# ESP32_breakout_v2_1.net
KiCad netlist of a schematic drawn in EAGLE
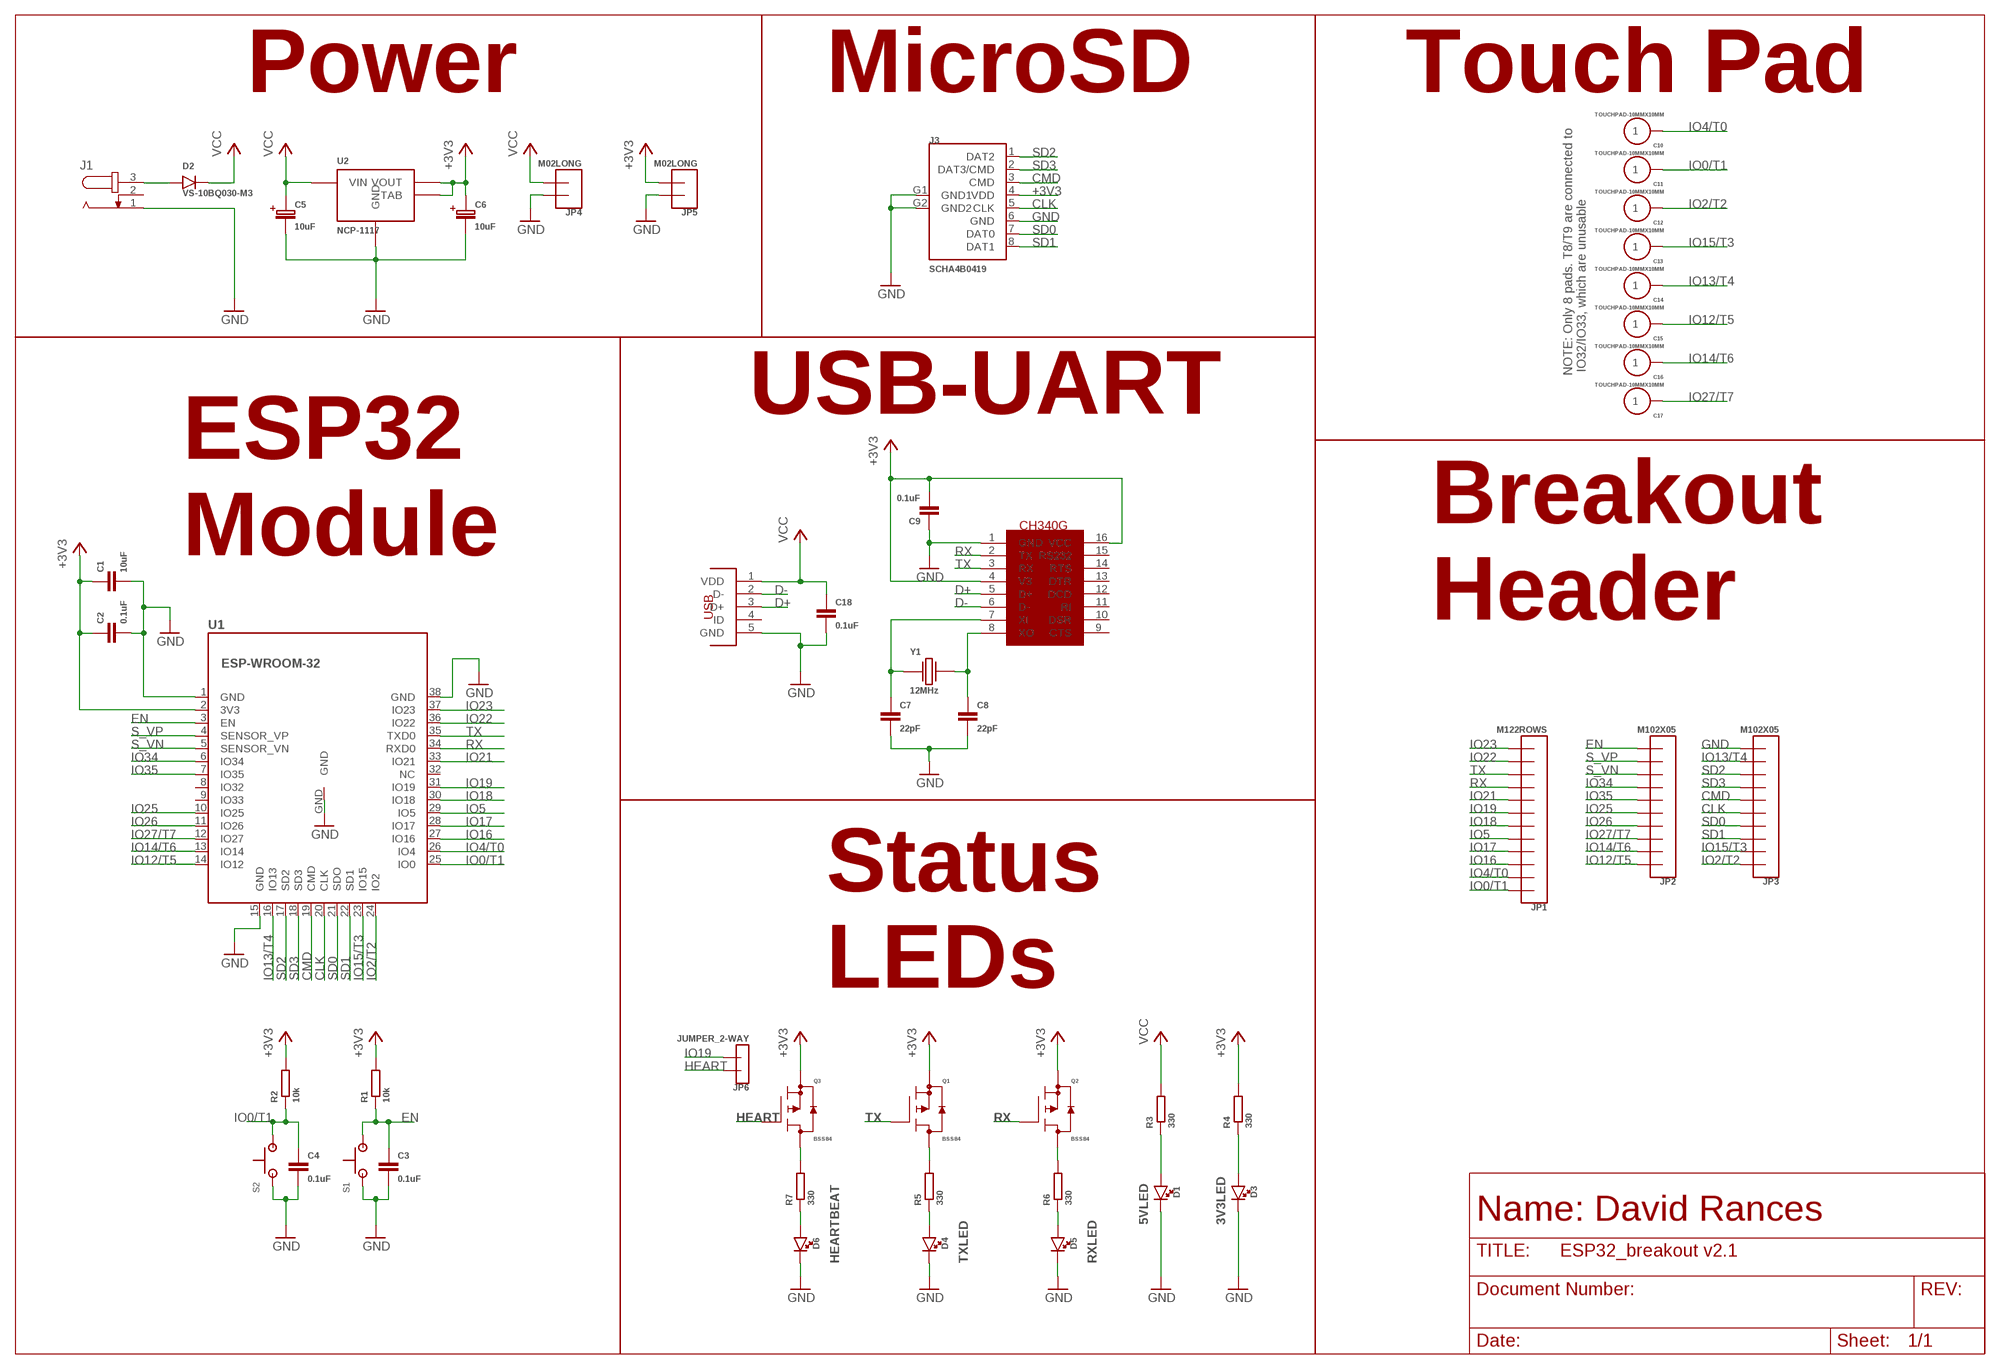
[diagram p0: schematic, sheet 1]

(export (version "E")
  (design (tool "Eeschema 10.0.6"))
  (components
    (comp (ref "C1")
      (value "10uF")
      (footprint "eagle-import:CAP-0603")
      (libsource (lib "eagle-import") (part "CAP0603"))
    )
    (comp (ref "C2")
      (value "0.1uF")
      (footprint "eagle-import:CAP-0603")
      (libsource (lib "eagle-import") (part "CAP0603"))
    )
    (comp (ref "C3")
      (value "0.1uF")
      (footprint "eagle-import:CAP-0603")
      (libsource (lib "eagle-import") (part "CAP0603"))
    )
    (comp (ref "C4")
      (value "0.1uF")
      (footprint "eagle-import:CAP-0603")
      (libsource (lib "eagle-import") (part "CAP0603"))
    )
    (comp (ref "C5")
      (value "10uF")
      (footprint "eagle-import:B-3528")
      (libsource (lib "eagle-import") (part "CAP-POLARCASEB-3528"))
    )
    (comp (ref "C6")
      (value "10uF")
      (footprint "eagle-import:B-3528")
      (libsource (lib "eagle-import") (part "CAP-POLARCASEB-3528"))
    )
    (comp (ref "C7")
      (value "22pF")
      (footprint "eagle-import:CAP-0603")
      (libsource (lib "eagle-import") (part "CAP0603"))
    )
    (comp (ref "C8")
      (value "22pF")
      (footprint "eagle-import:CAP-0603")
      (libsource (lib "eagle-import") (part "CAP0603"))
    )
    (comp (ref "C9")
      (value "0.1uF")
      (footprint "eagle-import:CAP-0603")
      (libsource (lib "eagle-import") (part "CAP0603"))
    )
    (comp (ref "C10")
      (value "TOUCHPAD-10MMX10MM")
      (footprint "eagle-import:TOUCH-10MMX10MM")
      (libsource (lib "eagle-import") (part "TOUCHPAD-10MMX10MM"))
    )
    (comp (ref "C11")
      (value "TOUCHPAD-10MMX10MM")
      (footprint "eagle-import:TOUCH-10MMX10MM")
      (libsource (lib "eagle-import") (part "TOUCHPAD-10MMX10MM"))
    )
    (comp (ref "C12")
      (value "TOUCHPAD-10MMX10MM")
      (footprint "eagle-import:TOUCH-10MMX10MM")
      (libsource (lib "eagle-import") (part "TOUCHPAD-10MMX10MM"))
    )
    (comp (ref "C13")
      (value "TOUCHPAD-10MMX10MM")
      (footprint "eagle-import:TOUCH-10MMX10MM")
      (libsource (lib "eagle-import") (part "TOUCHPAD-10MMX10MM"))
    )
    (comp (ref "C14")
      (value "TOUCHPAD-10MMX10MM")
      (footprint "eagle-import:TOUCH-10MMX10MM")
      (libsource (lib "eagle-import") (part "TOUCHPAD-10MMX10MM"))
    )
    (comp (ref "C15")
      (value "TOUCHPAD-10MMX10MM")
      (footprint "eagle-import:TOUCH-10MMX10MM")
      (libsource (lib "eagle-import") (part "TOUCHPAD-10MMX10MM"))
    )
    (comp (ref "C16")
      (value "TOUCHPAD-10MMX10MM")
      (footprint "eagle-import:TOUCH-10MMX10MM")
      (libsource (lib "eagle-import") (part "TOUCHPAD-10MMX10MM"))
    )
    (comp (ref "C17")
      (value "TOUCHPAD-10MMX10MM")
      (footprint "eagle-import:TOUCH-10MMX10MM")
      (libsource (lib "eagle-import") (part "TOUCHPAD-10MMX10MM"))
    )
    (comp (ref "C18")
      (value "0.1uF")
      (footprint "eagle-import:CAP-0603")
      (libsource (lib "eagle-import") (part "CAP0603"))
    )
    (comp (ref "D1")
      (value "LED1206")
      (footprint "eagle-import:LED-1206")
      (libsource (lib "eagle-import") (part "LED1206"))
    )
    (comp (ref "D2")
      (value "VS-10BQ030-M3")
      (footprint "eagle-import:DO-214AA")
      (libsource (lib "eagle-import") (part "VS-10BQ030-M3"))
    )
    (comp (ref "D3")
      (value "LED1206")
      (footprint "eagle-import:LED-1206")
      (libsource (lib "eagle-import") (part "LED1206"))
    )
    (comp (ref "D4")
      (value "LED1206")
      (footprint "eagle-import:LED-1206")
      (libsource (lib "eagle-import") (part "LED1206"))
    )
    (comp (ref "D5")
      (value "LED1206")
      (footprint "eagle-import:LED-1206")
      (libsource (lib "eagle-import") (part "LED1206"))
    )
    (comp (ref "D6")
      (value "LED1206")
      (footprint "eagle-import:LED-1206")
      (libsource (lib "eagle-import") (part "LED1206"))
    )
    (comp (ref "J1")
      (value "JACK-PLUG0")
      (footprint "eagle-import:SPC4077")
      (libsource (lib "eagle-import") (part "JACK-PLUG0"))
    )
    (comp (ref "J3")
      (value "SCHA4B0419")
      (footprint "eagle-import:MICROSD_SCHA4B0419")
      (libsource (lib "eagle-import") (part "SCHA4B0419"))
    )
    (comp (ref "JP1")
      (value "M122ROWS")
      (footprint "eagle-import:2X06")
      (libsource (lib "eagle-import") (part "M122ROWS"))
    )
    (comp (ref "JP2")
      (value "M102X05")
      (footprint "eagle-import:2X05")
      (libsource (lib "eagle-import") (part "M102X05"))
    )
    (comp (ref "JP3")
      (value "M102X05")
      (footprint "eagle-import:2X05")
      (libsource (lib "eagle-import") (part "M102X05"))
    )
    (comp (ref "JP4")
      (value "M02LONG")
      (footprint "eagle-import:1X02-LONG")
      (libsource (lib "eagle-import") (part "M02LONG"))
    )
    (comp (ref "JP5")
      (value "M02LONG")
      (footprint "eagle-import:1X02-LONG")
      (libsource (lib "eagle-import") (part "M02LONG"))
    )
    (comp (ref "JP6")
      (value "JUMPER_2-WAY")
      (footprint "eagle-import:1X02")
      (libsource (lib "eagle-import") (part "JUMPER_2-WAY"))
    )
    (comp (ref "Q1")
      (value "BSS84")
      (footprint "eagle-import:SOT-23-3")
      (libsource (lib "eagle-import") (part "BSS84"))
    )
    (comp (ref "Q2")
      (value "BSS84")
      (footprint "eagle-import:SOT-23-3")
      (libsource (lib "eagle-import") (part "BSS84"))
    )
    (comp (ref "Q3")
      (value "BSS84")
      (footprint "eagle-import:SOT-23-3")
      (libsource (lib "eagle-import") (part "BSS84"))
    )
    (comp (ref "R1")
      (value "10k")
      (footprint "eagle-import:RES-0603")
      (libsource (lib "eagle-import") (part "RESISTOR0603"))
    )
    (comp (ref "R2")
      (value "10k")
      (footprint "eagle-import:RES-0603")
      (libsource (lib "eagle-import") (part "RESISTOR0603"))
    )
    (comp (ref "R3")
      (value "330")
      (footprint "eagle-import:RES-0805")
      (libsource (lib "eagle-import") (part "RESISTOR0805"))
    )
    (comp (ref "R4")
      (value "330")
      (footprint "eagle-import:RES-0805")
      (libsource (lib "eagle-import") (part "RESISTOR0805"))
    )
    (comp (ref "R5")
      (value "330")
      (footprint "eagle-import:RES-0805")
      (libsource (lib "eagle-import") (part "RESISTOR0805"))
    )
    (comp (ref "R6")
      (value "330")
      (footprint "eagle-import:RES-0805")
      (libsource (lib "eagle-import") (part "RESISTOR0805"))
    )
    (comp (ref "R7")
      (value "330")
      (footprint "eagle-import:RES-0805")
      (libsource (lib "eagle-import") (part "RESISTOR0805"))
    )
    (comp (ref "S1")
      (value "PUSHBUTTONSKHMQME010")
      (footprint "eagle-import:SKHMQME010")
      (libsource (lib "eagle-import") (part "PUSHBUTTONSKHMQME010"))
    )
    (comp (ref "S2")
      (value "PUSHBUTTONSKHMQME010")
      (footprint "eagle-import:SKHMQME010")
      (libsource (lib "eagle-import") (part "PUSHBUTTONSKHMQME010"))
    )
    (comp (ref "U$4")
      (value "MOLEX_USBMICRO")
      (footprint "eagle-import:MOLEX_47346-001")
      (libsource (lib "eagle-import") (part "MOLEX_USBMICRO"))
    )
    (comp (ref "U$7")
      (value "CH340G")
      (footprint "eagle-import:SOIC16")
      (libsource (lib "eagle-import") (part "CH340G"))
    )
    (comp (ref "U1")
      (value "ESP-WROOM-32")
      (footprint "eagle-import:ESP-WROOM-32")
      (libsource (lib "eagle-import") (part "ESP-WROOM-32"))
    )
    (comp (ref "U2")
      (value "NCP-1117")
      (footprint "eagle-import:SOT-223-4")
      (libsource (lib "eagle-import") (part "NCP-1117"))
    )
    (comp (ref "Y1")
      (value "12MHz")
      (footprint "eagle-import:HC-49_US")
      (libsource (lib "eagle-import") (part "ABLS-12MHZ-B2-T"))
    )
  )
  (nets
    (net (code "1") (name "+3V3") (class "Default")
      (node (ref "C1") (pin "1") (pinfunction "1_1") (pintype "passive"))
      (node (ref "C2") (pin "1") (pinfunction "1_1") (pintype "passive"))
      (node (ref "C6") (pin "P") (pinfunction "P_P") (pintype "passive"))
      (node (ref "C9") (pin "2") (pinfunction "2_2") (pintype "passive"))
      (node (ref "J3") (pin "4") (pinfunction "VDD_4") (pintype "bidirectional"))
      (node (ref "JP5") (pin "2") (pinfunction "2_2") (pintype "bidirectional"))
      (node (ref "Q1") (pin "S") (pinfunction "S_S") (pintype "bidirectional"))
      (node (ref "Q2") (pin "S") (pinfunction "S_S") (pintype "bidirectional"))
      (node (ref "Q3") (pin "S") (pinfunction "S_S") (pintype "bidirectional"))
      (node (ref "R1") (pin "2") (pinfunction "2_2") (pintype "passive"))
      (node (ref "R2") (pin "2") (pinfunction "2_2") (pintype "passive"))
      (node (ref "R4") (pin "2") (pinfunction "2_2") (pintype "passive"))
      (node (ref "U$7") (pin "16") (pinfunction "VCC_16") (pintype "bidirectional"))
      (node (ref "U$7") (pin "4") (pinfunction "V3_4") (pintype "bidirectional"))
      (node (ref "U1") (pin "2") (pinfunction "3V3_2") (pintype "bidirectional"))
      (node (ref "U2") (pin "2") (pinfunction "VOUT_2") (pintype "power_in"))
      (node (ref "U2") (pin "PAD") (pinfunction "TAB_PAD") (pintype "power_in"))
    )
    (net (code "2") (name "/CLK") (class "Default")
      (node (ref "J3") (pin "5") (pinfunction "CLK_5") (pintype "bidirectional"))
      (node (ref "JP3") (pin "5") (pinfunction "5_5") (pintype "bidirectional"))
      (node (ref "U1") (pin "20") (pinfunction "CLK_20") (pintype "bidirectional"))
    )
    (net (code "3") (name "/CMD") (class "Default")
      (node (ref "J3") (pin "3") (pinfunction "CMD_3") (pintype "bidirectional"))
      (node (ref "JP3") (pin "6") (pinfunction "6_6") (pintype "bidirectional"))
      (node (ref "U1") (pin "19") (pinfunction "CMD_19") (pintype "bidirectional"))
    )
    (net (code "4") (name "/D+") (class "Default")
      (node (ref "U$4") (pin "3") (pinfunction "D+_3") (pintype "bidirectional"))
      (node (ref "U$7") (pin "5") (pinfunction "D+_5") (pintype "bidirectional"))
    )
    (net (code "5") (name "/D-") (class "Default")
      (node (ref "U$4") (pin "2") (pinfunction "D-_2") (pintype "bidirectional"))
      (node (ref "U$7") (pin "6") (pinfunction "D-_6") (pintype "bidirectional"))
    )
    (net (code "6") (name "/EN") (class "Default")
      (node (ref "C3") (pin "1") (pinfunction "1_1") (pintype "passive"))
      (node (ref "JP2") (pin "10") (pinfunction "10_10") (pintype "bidirectional"))
      (node (ref "R1") (pin "1") (pinfunction "1_1") (pintype "passive"))
      (node (ref "S1") (pin "3") (pinfunction "2_3") (pintype "bidirectional"))
      (node (ref "S1") (pin "4") (pinfunction "2_4") (pintype "bidirectional"))
      (node (ref "U1") (pin "3") (pinfunction "EN_3") (pintype "bidirectional"))
    )
    (net (code "7") (name "/HEART") (class "Default")
      (node (ref "JP6") (pin "1") (pinfunction "1_1") (pintype "bidirectional"))
      (node (ref "Q3") (pin "G") (pinfunction "G_G") (pintype "bidirectional"))
    )
    (net (code "8") (name "/IO0{slash}T1") (class "Default")
      (node (ref "C11") (pin "P$1") (pinfunction "1_P$1") (pintype "bidirectional"))
      (node (ref "C4") (pin "1") (pinfunction "1_1") (pintype "passive"))
      (node (ref "JP1") (pin "1") (pinfunction "1_1") (pintype "bidirectional"))
      (node (ref "R2") (pin "1") (pinfunction "1_1") (pintype "passive"))
      (node (ref "S2") (pin "3") (pinfunction "2_3") (pintype "bidirectional"))
      (node (ref "S2") (pin "4") (pinfunction "2_4") (pintype "bidirectional"))
      (node (ref "U1") (pin "25") (pinfunction "IO0_25") (pintype "bidirectional"))
    )
    (net (code "9") (name "/IO2{slash}T2") (class "Default")
      (node (ref "C12") (pin "P$1") (pinfunction "1_P$1") (pintype "bidirectional"))
      (node (ref "JP3") (pin "1") (pinfunction "1_1") (pintype "bidirectional"))
      (node (ref "U1") (pin "24") (pinfunction "IO2_24") (pintype "bidirectional"))
    )
    (net (code "10") (name "/IO4{slash}T0") (class "Default")
      (node (ref "C10") (pin "P$1") (pinfunction "1_P$1") (pintype "bidirectional"))
      (node (ref "JP1") (pin "2") (pinfunction "2_2") (pintype "bidirectional"))
      (node (ref "U1") (pin "26") (pinfunction "IO4_26") (pintype "bidirectional"))
    )
    (net (code "11") (name "/IO5") (class "Default")
      (node (ref "JP1") (pin "5") (pinfunction "5_5") (pintype "bidirectional"))
      (node (ref "U1") (pin "29") (pinfunction "IO5_29") (pintype "bidirectional"))
    )
    (net (code "12") (name "/IO12{slash}T5") (class "Default")
      (node (ref "C15") (pin "P$1") (pinfunction "1_P$1") (pintype "bidirectional"))
      (node (ref "JP2") (pin "1") (pinfunction "1_1") (pintype "bidirectional"))
      (node (ref "U1") (pin "14") (pinfunction "IO12_14") (pintype "bidirectional"))
    )
    (net (code "13") (name "/IO13{slash}T4") (class "Default")
      (node (ref "C14") (pin "P$1") (pinfunction "1_P$1") (pintype "bidirectional"))
      (node (ref "JP3") (pin "9") (pinfunction "9_9") (pintype "bidirectional"))
      (node (ref "U1") (pin "16") (pinfunction "IO13_16") (pintype "bidirectional"))
    )
    (net (code "14") (name "/IO14{slash}T6") (class "Default")
      (node (ref "C16") (pin "P$1") (pinfunction "1_P$1") (pintype "bidirectional"))
      (node (ref "JP2") (pin "2") (pinfunction "2_2") (pintype "bidirectional"))
      (node (ref "U1") (pin "13") (pinfunction "IO14_13") (pintype "bidirectional"))
    )
    (net (code "15") (name "/IO15{slash}T3") (class "Default")
      (node (ref "C13") (pin "P$1") (pinfunction "1_P$1") (pintype "bidirectional"))
      (node (ref "JP3") (pin "2") (pinfunction "2_2") (pintype "bidirectional"))
      (node (ref "U1") (pin "23") (pinfunction "IO15_23") (pintype "bidirectional"))
    )
    (net (code "16") (name "/IO16") (class "Default")
      (node (ref "JP1") (pin "3") (pinfunction "3_3") (pintype "bidirectional"))
      (node (ref "U1") (pin "27") (pinfunction "IO16_27") (pintype "bidirectional"))
    )
    (net (code "17") (name "/IO17") (class "Default")
      (node (ref "JP1") (pin "4") (pinfunction "4_4") (pintype "bidirectional"))
      (node (ref "U1") (pin "28") (pinfunction "IO17_28") (pintype "bidirectional"))
    )
    (net (code "18") (name "/IO18") (class "Default")
      (node (ref "JP1") (pin "6") (pinfunction "6_6") (pintype "bidirectional"))
      (node (ref "U1") (pin "30") (pinfunction "IO18_30") (pintype "bidirectional"))
    )
    (net (code "19") (name "/IO19") (class "Default")
      (node (ref "JP1") (pin "7") (pinfunction "7_7") (pintype "bidirectional"))
      (node (ref "JP6") (pin "2") (pinfunction "2_2") (pintype "bidirectional"))
      (node (ref "U1") (pin "31") (pinfunction "IO19_31") (pintype "bidirectional"))
    )
    (net (code "20") (name "/IO21") (class "Default")
      (node (ref "JP1") (pin "8") (pinfunction "8_8") (pintype "bidirectional"))
      (node (ref "U1") (pin "33") (pinfunction "IO21_33") (pintype "bidirectional"))
    )
    (net (code "21") (name "/IO22") (class "Default")
      (node (ref "JP1") (pin "11") (pinfunction "11_11") (pintype "bidirectional"))
      (node (ref "U1") (pin "36") (pinfunction "IO22_36") (pintype "bidirectional"))
    )
    (net (code "22") (name "/IO23") (class "Default")
      (node (ref "JP1") (pin "12") (pinfunction "12_12") (pintype "bidirectional"))
      (node (ref "U1") (pin "37") (pinfunction "IO23_37") (pintype "bidirectional"))
    )
    (net (code "23") (name "/IO25") (class "Default")
      (node (ref "JP2") (pin "5") (pinfunction "5_5") (pintype "bidirectional"))
      (node (ref "U1") (pin "10") (pinfunction "IO25_10") (pintype "bidirectional"))
    )
    (net (code "24") (name "/IO26") (class "Default")
      (node (ref "JP2") (pin "4") (pinfunction "4_4") (pintype "bidirectional"))
      (node (ref "U1") (pin "11") (pinfunction "IO26_11") (pintype "bidirectional"))
    )
    (net (code "25") (name "/IO27{slash}T7") (class "Default")
      (node (ref "C17") (pin "P$1") (pinfunction "1_P$1") (pintype "bidirectional"))
      (node (ref "JP2") (pin "3") (pinfunction "3_3") (pintype "bidirectional"))
      (node (ref "U1") (pin "12") (pinfunction "IO27_12") (pintype "bidirectional"))
    )
    (net (code "26") (name "/IO34") (class "Default")
      (node (ref "JP2") (pin "7") (pinfunction "7_7") (pintype "bidirectional"))
      (node (ref "U1") (pin "6") (pinfunction "IO34_6") (pintype "bidirectional"))
    )
    (net (code "27") (name "/IO35") (class "Default")
      (node (ref "JP2") (pin "6") (pinfunction "6_6") (pintype "bidirectional"))
      (node (ref "U1") (pin "7") (pinfunction "IO35_7") (pintype "bidirectional"))
    )
    (net (code "28") (name "/RX") (class "Default")
      (node (ref "JP1") (pin "9") (pinfunction "9_9") (pintype "bidirectional"))
      (node (ref "Q2") (pin "G") (pinfunction "G_G") (pintype "bidirectional"))
      (node (ref "U$7") (pin "2") (pinfunction "TX_2") (pintype "bidirectional"))
      (node (ref "U1") (pin "34") (pinfunction "RXD0_34") (pintype "bidirectional"))
    )
    (net (code "29") (name "/SD0") (class "Default")
      (node (ref "J3") (pin "7") (pinfunction "DAT0_7") (pintype "bidirectional"))
      (node (ref "JP3") (pin "4") (pinfunction "4_4") (pintype "bidirectional"))
      (node (ref "U1") (pin "21") (pinfunction "SDO_21") (pintype "bidirectional"))
    )
    (net (code "30") (name "/SD1") (class "Default")
      (node (ref "J3") (pin "8") (pinfunction "DAT1_8") (pintype "bidirectional"))
      (node (ref "JP3") (pin "3") (pinfunction "3_3") (pintype "bidirectional"))
      (node (ref "U1") (pin "22") (pinfunction "SD1_22") (pintype "bidirectional"))
    )
    (net (code "31") (name "/SD2") (class "Default")
      (node (ref "J3") (pin "1") (pinfunction "DAT2_1") (pintype "bidirectional"))
      (node (ref "JP3") (pin "8") (pinfunction "8_8") (pintype "bidirectional"))
      (node (ref "U1") (pin "17") (pinfunction "SD2_17") (pintype "bidirectional"))
    )
    (net (code "32") (name "/SD3") (class "Default")
      (node (ref "J3") (pin "2") (pinfunction "DAT3/CMD_2") (pintype "bidirectional"))
      (node (ref "JP3") (pin "7") (pinfunction "7_7") (pintype "bidirectional"))
      (node (ref "U1") (pin "18") (pinfunction "SD3_18") (pintype "bidirectional"))
    )
    (net (code "33") (name "/S_VN") (class "Default")
      (node (ref "JP2") (pin "8") (pinfunction "8_8") (pintype "bidirectional"))
      (node (ref "U1") (pin "5") (pinfunction "SENSOR_VN_5") (pintype "bidirectional"))
    )
    (net (code "34") (name "/S_VP") (class "Default")
      (node (ref "JP2") (pin "9") (pinfunction "9_9") (pintype "bidirectional"))
      (node (ref "U1") (pin "4") (pinfunction "SENSOR_VP_4") (pintype "bidirectional"))
    )
    (net (code "35") (name "/TX") (class "Default")
      (node (ref "JP1") (pin "10") (pinfunction "10_10") (pintype "bidirectional"))
      (node (ref "Q1") (pin "G") (pinfunction "G_G") (pintype "bidirectional"))
      (node (ref "U$7") (pin "3") (pinfunction "RX_3") (pintype "bidirectional"))
      (node (ref "U1") (pin "35") (pinfunction "TXD0_35") (pintype "bidirectional"))
    )
    (net (code "36") (name "GND") (class "Default")
      (node (ref "C1") (pin "2") (pinfunction "2_2") (pintype "passive"))
      (node (ref "C18") (pin "2") (pinfunction "2_2") (pintype "passive"))
      (node (ref "C2") (pin "2") (pinfunction "2_2") (pintype "passive"))
      (node (ref "C3") (pin "2") (pinfunction "2_2") (pintype "passive"))
      (node (ref "C4") (pin "2") (pinfunction "2_2") (pintype "passive"))
      (node (ref "C5") (pin "N") (pinfunction "N_N") (pintype "passive"))
      (node (ref "C6") (pin "N") (pinfunction "N_N") (pintype "passive"))
      (node (ref "C7") (pin "2") (pinfunction "2_2") (pintype "passive"))
      (node (ref "C8") (pin "2") (pinfunction "2_2") (pintype "passive"))
      (node (ref "C9") (pin "1") (pinfunction "1_1") (pintype "passive"))
      (node (ref "D1") (pin "C") (pinfunction "C_C") (pintype "bidirectional"))
      (node (ref "D3") (pin "C") (pinfunction "C_C") (pintype "bidirectional"))
      (node (ref "D4") (pin "C") (pinfunction "C_C") (pintype "bidirectional"))
      (node (ref "D5") (pin "C") (pinfunction "C_C") (pintype "bidirectional"))
      (node (ref "D6") (pin "C") (pinfunction "C_C") (pintype "bidirectional"))
      (node (ref "J1") (pin "1") (pinfunction "1_1") (pintype "passive"))
      (node (ref "J3") (pin "6") (pinfunction "GND_6") (pintype "bidirectional"))
      (node (ref "J3") (pin "G1") (pinfunction "GND1_G1") (pintype "bidirectional"))
      (node (ref "J3") (pin "G2") (pinfunction "GND2_G2") (pintype "bidirectional"))
      (node (ref "JP3") (pin "10") (pinfunction "10_10") (pintype "bidirectional"))
      (node (ref "JP4") (pin "1") (pinfunction "1_1") (pintype "bidirectional"))
      (node (ref "JP5") (pin "1") (pinfunction "1_1") (pintype "bidirectional"))
      (node (ref "S1") (pin "1") (pinfunction "1_1") (pintype "bidirectional"))
      (node (ref "S1") (pin "2") (pinfunction "1_2") (pintype "bidirectional"))
      (node (ref "S2") (pin "1") (pinfunction "1_1") (pintype "bidirectional"))
      (node (ref "S2") (pin "2") (pinfunction "1_2") (pintype "bidirectional"))
      (node (ref "U$4") (pin "5") (pinfunction "GND_5") (pintype "bidirectional"))
      (node (ref "U$7") (pin "1") (pinfunction "GND_1") (pintype "bidirectional"))
      (node (ref "U1") (pin "1") (pinfunction "GND_1") (pintype "bidirectional"))
      (node (ref "U1") (pin "15") (pinfunction "GND_15") (pintype "bidirectional"))
      (node (ref "U1") (pin "38") (pinfunction "GND_38") (pintype "bidirectional"))
      (node (ref "U1") (pin "GND") (pinfunction "GND_GND") (pintype "bidirectional"))
      (node (ref "U2") (pin "1") (pinfunction "GND_1") (pintype "power_in"))
    )
    (net (code "37") (name "Net-(D1-PadA)") (class "Default")
      (node (ref "D1") (pin "A") (pinfunction "A_A") (pintype "bidirectional"))
      (node (ref "R3") (pin "1") (pinfunction "1_1") (pintype "passive"))
    )
    (net (code "38") (name "Net-(D2-PadA)") (class "Default")
      (node (ref "D2") (pin "A") (pinfunction "A_A") (pintype "bidirectional"))
      (node (ref "J1") (pin "3") (pinfunction "3_3") (pintype "passive"))
    )
    (net (code "39") (name "Net-(D3-PadA)") (class "Default")
      (node (ref "D3") (pin "A") (pinfunction "A_A") (pintype "bidirectional"))
      (node (ref "R4") (pin "1") (pinfunction "1_1") (pintype "passive"))
    )
    (net (code "40") (name "Net-(D4-PadA)") (class "Default")
      (node (ref "D4") (pin "A") (pinfunction "A_A") (pintype "bidirectional"))
      (node (ref "R5") (pin "1") (pinfunction "1_1") (pintype "passive"))
    )
    (net (code "41") (name "Net-(D5-PadA)") (class "Default")
      (node (ref "D5") (pin "A") (pinfunction "A_A") (pintype "bidirectional"))
      (node (ref "R6") (pin "1") (pinfunction "1_1") (pintype "passive"))
    )
    (net (code "42") (name "Net-(D6-PadA)") (class "Default")
      (node (ref "D6") (pin "A") (pinfunction "A_A") (pintype "bidirectional"))
      (node (ref "R7") (pin "1") (pinfunction "1_1") (pintype "passive"))
    )
    (net (code "43") (name "Net-(Q1-PadD)") (class "Default")
      (node (ref "Q1") (pin "D") (pinfunction "D_D") (pintype "bidirectional"))
      (node (ref "R5") (pin "2") (pinfunction "2_2") (pintype "passive"))
    )
    (net (code "44") (name "Net-(Q2-PadD)") (class "Default")
      (node (ref "Q2") (pin "D") (pinfunction "D_D") (pintype "bidirectional"))
      (node (ref "R6") (pin "2") (pinfunction "2_2") (pintype "passive"))
    )
    (net (code "45") (name "Net-(Q3-PadD)") (class "Default")
      (node (ref "Q3") (pin "D") (pinfunction "D_D") (pintype "bidirectional"))
      (node (ref "R7") (pin "2") (pinfunction "2_2") (pintype "passive"))
    )
    (net (code "46") (name "Net-(U$7-XI)") (class "Default")
      (node (ref "C7") (pin "1") (pinfunction "1_1") (pintype "passive"))
      (node (ref "U$7") (pin "7") (pinfunction "XI_7") (pintype "bidirectional"))
      (node (ref "Y1") (pin "P$1") (pinfunction "1_P$1") (pintype "bidirectional"))
    )
    (net (code "47") (name "Net-(U$7-XO)") (class "Default")
      (node (ref "C8") (pin "1") (pinfunction "1_1") (pintype "passive"))
      (node (ref "U$7") (pin "8") (pinfunction "XO_8") (pintype "bidirectional"))
      (node (ref "Y1") (pin "P$2") (pinfunction "2_P$2") (pintype "bidirectional"))
    )
    (net (code "48") (name "VCC") (class "Default")
      (node (ref "C18") (pin "1") (pinfunction "1_1") (pintype "passive"))
      (node (ref "C5") (pin "P") (pinfunction "P_P") (pintype "passive"))
      (node (ref "D2") (pin "C") (pinfunction "C_C") (pintype "bidirectional"))
      (node (ref "JP4") (pin "2") (pinfunction "2_2") (pintype "bidirectional"))
      (node (ref "R3") (pin "2") (pinfunction "2_2") (pintype "passive"))
      (node (ref "U$4") (pin "1") (pinfunction "VDD_1") (pintype "bidirectional"))
      (node (ref "U2") (pin "3") (pinfunction "VIN_3") (pintype "power_in"))
    )
    (net (code "49") (name "unconnected-(J1-Pad2)") (class "Default")
      (node (ref "J1") (pin "2") (pinfunction "2_2") (pintype "passive"))
    )
    (net (code "50") (name "unconnected-(S1-3-Pad5)") (class "Default")
      (node (ref "S1") (pin "5") (pinfunction "3_5") (pintype "bidirectional"))
    )
    (net (code "51") (name "unconnected-(S2-3-Pad5)") (class "Default")
      (node (ref "S2") (pin "5") (pinfunction "3_5") (pintype "bidirectional"))
    )
    (net (code "52") (name "unconnected-(U$4-ID-Pad4)") (class "Default")
      (node (ref "U$4") (pin "4") (pinfunction "ID_4") (pintype "bidirectional"))
    )
    (net (code "53") (name "unconnected-(U$7-CTS-Pad9)") (class "Default")
      (node (ref "U$7") (pin "9") (pinfunction "CTS_9") (pintype "bidirectional"))
    )
    (net (code "54") (name "unconnected-(U$7-DCD-Pad12)") (class "Default")
      (node (ref "U$7") (pin "12") (pinfunction "DCD_12") (pintype "bidirectional"))
    )
    (net (code "55") (name "unconnected-(U$7-DSR-Pad10)") (class "Default")
      (node (ref "U$7") (pin "10") (pinfunction "DSR_10") (pintype "bidirectional"))
    )
    (net (code "56") (name "unconnected-(U$7-DTR-Pad13)") (class "Default")
      (node (ref "U$7") (pin "13") (pinfunction "DTR_13") (pintype "bidirectional"))
    )
    (net (code "57") (name "unconnected-(U$7-RI-Pad11)") (class "Default")
      (node (ref "U$7") (pin "11") (pinfunction "RI_11") (pintype "bidirectional"))
    )
    (net (code "58") (name "unconnected-(U$7-RS232-Pad15)") (class "Default")
      (node (ref "U$7") (pin "15") (pinfunction "RS232_15") (pintype "bidirectional"))
    )
    (net (code "59") (name "unconnected-(U$7-RTS-Pad14)") (class "Default")
      (node (ref "U$7") (pin "14") (pinfunction "RTS_14") (pintype "bidirectional"))
    )
    (net (code "60") (name "unconnected-(U1-IO32-Pad8)") (class "Default")
      (node (ref "U1") (pin "8") (pinfunction "IO32_8") (pintype "bidirectional"))
    )
    (net (code "61") (name "unconnected-(U1-IO33-Pad9)") (class "Default")
      (node (ref "U1") (pin "9") (pinfunction "IO33_9") (pintype "bidirectional"))
    )
    (net (code "62") (name "unconnected-(U1-NC-Pad32)") (class "Default")
      (node (ref "U1") (pin "32") (pinfunction "NC_32") (pintype "bidirectional"))
    )
  )
)
